# Main.net
KiCad netlist of a schematic drawn in Altium Designer
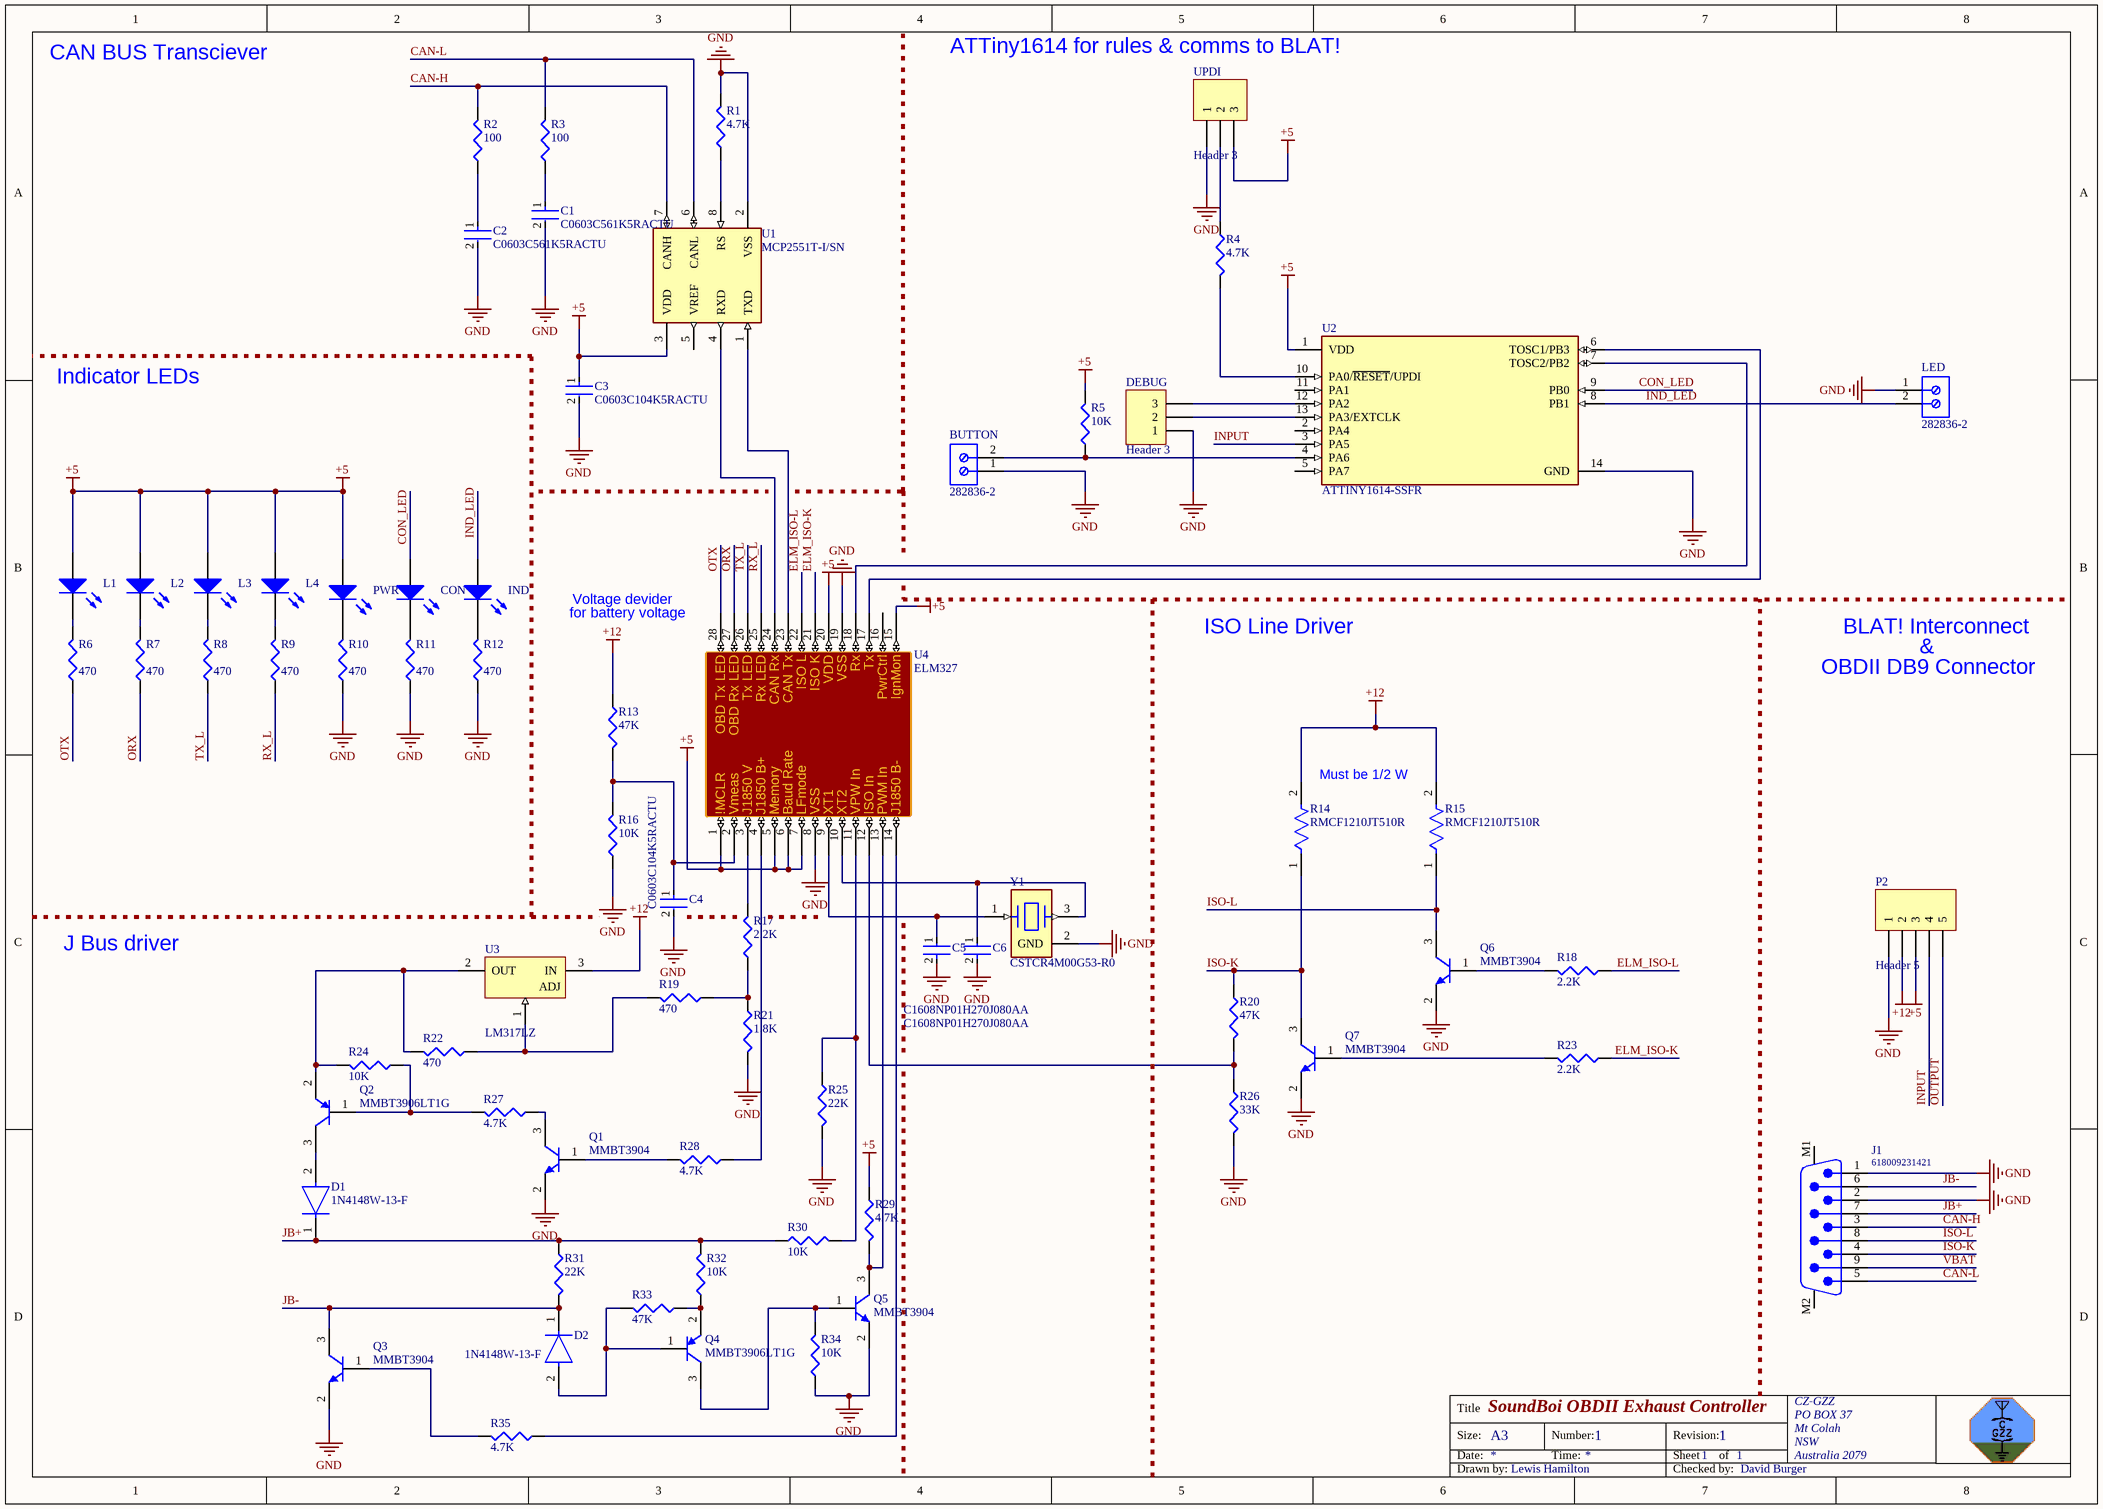
[diagram p0: Main.SchDoc]

(export (version "E")
  (design (tool "Eeschema 10.0.6"))
  (components
    (comp (ref "BUTTON")
      (value "282836-2")
      (footprint "TECO-282836-2_V")
      (description "Female Header, Pitch 5 mm, 1 x 2 Position, Height 10 mm, Tail Length 3.5 mm, Rohs, Bulk")
      (fields (field (name "VOLTAGE") "300V") (field (name "MANUFACTURER") "TE Connectivity"))
      (libsource (lib "Altium Content Vault") (part "CN-1P-F-TB2"))
    )
    (comp (ref "C1")
      (value "C0603C561K5RACTU")
      (footprint "FP-C0603C-CF-MFG")
      (description "CAP CER 560PF 50V X7R 0603")
      (fields
        (field (name "TOLERANCE") "0.1")
        (field (name "OCTOPART") "https://octopart.com/c0603c561k5ractu-kemet-138569")
      )
      (libsource (lib "Altium Content Vault") (part "b4654b650e69147ec39a6b967a45e02"))
    )
    (comp (ref "C2")
      (value "C0603C561K5RACTU")
      (footprint "FP-C0603C-CF-MFG")
      (description "CAP CER 560PF 50V X7R 0603")
      (fields
        (field (name "TOLERANCE") "0.1")
        (field (name "OCTOPART") "https://octopart.com/c0603c561k5ractu-kemet-138569")
      )
      (libsource (lib "Altium Content Vault") (part "b4654b650e69147ec39a6b967a45e02"))
    )
    (comp (ref "C3")
      (value "C0603C104K5RACTU")
      (footprint "FP-C0603C-CF-MFG")
      (description "CAP CER 0.1UF 50V X7R 0603")
      (fields (field (name "TOLERANCE") "0.1") (field (name "MANUFACTURER") "KEMET"))
      (libsource (lib "Altium Content Vault") (part "b4654b650e69147ec39a6b967a45e02"))
    )
    (comp (ref "C4")
      (value "C0603C104K5RACTU")
      (footprint "FP-C0603C-CF-MFG")
      (description "CAP CER 0.1UF 50V X7R 0603")
      (fields (field (name "TOLERANCE") "0.1") (field (name "MANUFACTURER") "KEMET"))
      (libsource (lib "Altium Content Vault") (part "b4654b650e69147ec39a6b967a45e02"))
    )
    (comp (ref "C5")
      (value "C1608NP01H270J080AA")
      (footprint "FP-C1608-080-0_1-IPC_A")
      (description "Multilayer Ceramic Capacitors 27pF ±5% 50V NP0 SMD 0603")
      (fields (field (name "TOLERANCE") "5%"))
      (libsource (lib "Altium Content Vault") (part "236180d848d6139a670b325ea6854c9"))
    )
    (comp (ref "C6")
      (value "C1608NP01H270J080AA")
      (footprint "FP-C1608-080-0_1-IPC_A")
      (description "Multilayer Ceramic Capacitors 27pF ±5% 50V NP0 SMD 0603")
      (fields (field (name "TOLERANCE") "5%"))
      (libsource (lib "Altium Content Vault") (part "236180d848d6139a670b325ea6854c9"))
    )
    (comp (ref "CON")
      (value "LED2")
      (footprint "3.2X1.6X1.1")
      (description "Typical RED, GREEN, YELLOW, AMBER GaAs LED")
      (fields (field (name "PUBLISHER") "Altium Limited"))
      (libsource (lib "Miscellaneous Devices") (part "LED2"))
    )
    (comp (ref "D1")
      (value "1N4148W-13-F")
      (footprint "FP-SOD123-MFG")
      (description "DIODE GEN PURP 100V 150MA SOD123")
      (fields
        (field (name "OCTOPART") "https://octopart.com/1n4148w-13-f-diodes+inc.-2359612")
        (field (name "MANUFACTURER") "Diodes Inc.")
      )
      (libsource (lib "Altium Content Vault") (part "d7152d700b627762746794eb795d46e"))
    )
    (comp (ref "D2")
      (value "1N4148W-13-F")
      (footprint "FP-SOD123-MFG")
      (description "DIODE GEN PURP 100V 150MA SOD123")
      (fields
        (field (name "OCTOPART") "https://octopart.com/1n4148w-13-f-diodes+inc.-2359612")
        (field (name "MANUFACTURER") "Diodes Inc.")
      )
      (libsource (lib "Altium Content Vault") (part "d7152d700b627762746794eb795d46e"))
    )
    (comp (ref "DEBUG")
      (value "Header 3")
      (footprint "HDR1X3")
      (description "Header, 3-Pin")
      (fields (field (name "PUBLISHER") "Altium Limited"))
      (libsource (lib "Miscellaneous Connectors") (part "Header 3"))
    )
    (comp (ref "IND")
      (value "LED2")
      (footprint "3.2X1.6X1.1")
      (description "Typical RED, GREEN, YELLOW, AMBER GaAs LED")
      (fields (field (name "PUBLISHER") "Altium Limited"))
      (libsource (lib "Miscellaneous Devices") (part "LED2"))
    )
    (comp (ref "J1")
      (value "618009231421")
      (footprint "618009231421")
      (description "Male PCB Connector with Hex Screw WR-DSUB, 10.30 mm, Angled, 9 pins")
      (fields (field (name "MANUFACTURER") "Wurth Elektronik") (field (name "PUBLISHER") "WurthElektronik"))
      (libsource (lib "Altium Content Vault") (part "WE-CN-2S-2M-D9"))
    )
    (comp (ref "L1")
      (value "LED2")
      (footprint "3.2X1.6X1.1")
      (description "Typical RED, GREEN, YELLOW, AMBER GaAs LED")
      (fields (field (name "PUBLISHER") "Altium Limited"))
      (libsource (lib "Miscellaneous Devices") (part "LED2"))
    )
    (comp (ref "L2")
      (value "LED2")
      (footprint "3.2X1.6X1.1")
      (description "Typical RED, GREEN, YELLOW, AMBER GaAs LED")
      (fields (field (name "PUBLISHER") "Altium Limited"))
      (libsource (lib "Miscellaneous Devices") (part "LED2"))
    )
    (comp (ref "L3")
      (value "LED2")
      (footprint "3.2X1.6X1.1")
      (description "Typical RED, GREEN, YELLOW, AMBER GaAs LED")
      (fields (field (name "PUBLISHER") "Altium Limited"))
      (libsource (lib "Miscellaneous Devices") (part "LED2"))
    )
    (comp (ref "L4")
      (value "LED2")
      (footprint "3.2X1.6X1.1")
      (description "Typical RED, GREEN, YELLOW, AMBER GaAs LED")
      (fields (field (name "PUBLISHER") "Altium Limited"))
      (libsource (lib "Miscellaneous Devices") (part "LED2"))
    )
    (comp (ref "LED")
      (value "282836-2")
      (footprint "TECO-282836-2_V")
      (description "Female Header, Pitch 5 mm, 1 x 2 Position, Height 10 mm, Tail Length 3.5 mm, Rohs, Bulk")
      (fields (field (name "VOLTAGE") "300V") (field (name "MANUFACTURER") "TE Connectivity"))
      (libsource (lib "Altium Content Vault") (part "CN-1P-F-TB2"))
    )
    (comp (ref "P2")
      (value "Header 5")
      (footprint "HDR1X5")
      (description "Header, 5-Pin")
      (fields (field (name "PUBLISHER") "Altium Limited"))
      (libsource (lib "Miscellaneous Connectors") (part "Header 5"))
    )
    (comp (ref "PWR")
      (value "LED2")
      (footprint "3.2X1.6X1.1")
      (description "Typical RED, GREEN, YELLOW, AMBER GaAs LED")
      (fields (field (name "PUBLISHER") "Altium Limited"))
      (libsource (lib "Miscellaneous Devices") (part "LED2"))
    )
    (comp (ref "Q1")
      (value "MMBT3904")
      (footprint "FAIR-SOT23-3_V")
      (description "NPN General Purpose Amplifier, 40 V, 0.2 A, -55 to 150 degC, 3-Pin SOT23, RoHS, Tape and Reel")
      (fields (field (name "TOLERANCE") "30ppm"))
      (libsource (lib "Altium Content Vault") (part "BJT-NPN-BEC-3"))
    )
    (comp (ref "Q2")
      (value "MMBT3906LT1G")
      (footprint "ONSC-SOT-23-3-318-08_V")
      (description "General Purpose Transistor, PNP Silicon, 3-Pin SOT-23, Pb-Free, Tape and Reel")
      (fields (field (name "MANUFACTURER") "On Semiconductor"))
      (libsource (lib "Altium Content Vault") (part "ONSC-PNP-B1E2C3-3"))
    )
    (comp (ref "Q3")
      (value "MMBT3904")
      (footprint "FAIR-SOT23-3_V")
      (description "NPN General Purpose Amplifier, 40 V, 0.2 A, -55 to 150 degC, 3-Pin SOT23, RoHS, Tape and Reel")
      (fields (field (name "TOLERANCE") "30ppm"))
      (libsource (lib "Altium Content Vault") (part "BJT-NPN-BEC-3"))
    )
    (comp (ref "Q4")
      (value "MMBT3906LT1G")
      (footprint "ONSC-SOT-23-3-318-08_V")
      (description "General Purpose Transistor, PNP Silicon, 3-Pin SOT-23, Pb-Free, Tape and Reel")
      (fields (field (name "MANUFACTURER") "On Semiconductor"))
      (libsource (lib "Altium Content Vault") (part "ONSC-PNP-B1E2C3-3"))
    )
    (comp (ref "Q5")
      (value "MMBT3904")
      (footprint "FAIR-SOT23-3_V")
      (description "NPN General Purpose Amplifier, 40 V, 0.2 A, -55 to 150 degC, 3-Pin SOT23, RoHS, Tape and Reel")
      (fields (field (name "TOLERANCE") "30ppm"))
      (libsource (lib "Altium Content Vault") (part "BJT-NPN-BEC-3"))
    )
    (comp (ref "Q6")
      (value "MMBT3904")
      (footprint "FAIR-SOT23-3_V")
      (description "NPN General Purpose Amplifier, 40 V, 0.2 A, -55 to 150 degC, 3-Pin SOT23, RoHS, Tape and Reel")
      (fields (field (name "TOLERANCE") "30ppm"))
      (libsource (lib "Altium Content Vault") (part "BJT-NPN-BEC-3"))
    )
    (comp (ref "Q7")
      (value "MMBT3904")
      (footprint "FAIR-SOT23-3_V")
      (description "NPN General Purpose Amplifier, 40 V, 0.2 A, -55 to 150 degC, 3-Pin SOT23, RoHS, Tape and Reel")
      (fields (field (name "TOLERANCE") "30ppm"))
      (libsource (lib "Altium Content Vault") (part "BJT-NPN-BEC-3"))
    )
    (comp (ref "R1")
      (value "4.7K")
      (footprint "J1-0603")
      (description "Resistor")
      (fields (field (name "Comment") "Res3") (field (name "PUBLISHER") "Altium Limited"))
      (libsource (lib "Miscellaneous Devices") (part "Res3"))
    )
    (comp (ref "R2")
      (value "100")
      (footprint "J1-0603")
      (description "Resistor")
      (fields (field (name "Comment") "Res3") (field (name "PUBLISHER") "Altium Limited"))
      (libsource (lib "Miscellaneous Devices") (part "Res3"))
    )
    (comp (ref "R3")
      (value "100")
      (footprint "J1-0603")
      (description "Resistor")
      (fields (field (name "Comment") "Res3") (field (name "PUBLISHER") "Altium Limited"))
      (libsource (lib "Miscellaneous Devices") (part "Res3"))
    )
    (comp (ref "R4")
      (value "4.7K")
      (footprint "J1-0603")
      (description "Resistor")
      (fields (field (name "Comment") "Res3") (field (name "PUBLISHER") "Altium Limited"))
      (libsource (lib "Miscellaneous Devices") (part "Res3"))
    )
    (comp (ref "R5")
      (value "10K")
      (footprint "J1-0603")
      (description "Resistor")
      (fields (field (name "Comment") "Res3") (field (name "PUBLISHER") "Altium Limited"))
      (libsource (lib "Miscellaneous Devices") (part "Res3"))
    )
    (comp (ref "R6")
      (value "470")
      (footprint "J1-0603")
      (description "Resistor")
      (fields (field (name "Comment") "Res3") (field (name "PUBLISHER") "Altium Limited"))
      (libsource (lib "Miscellaneous Devices") (part "Res3"))
    )
    (comp (ref "R7")
      (value "470")
      (footprint "J1-0603")
      (description "Resistor")
      (fields (field (name "Comment") "Res3") (field (name "PUBLISHER") "Altium Limited"))
      (libsource (lib "Miscellaneous Devices") (part "Res3"))
    )
    (comp (ref "R8")
      (value "470")
      (footprint "J1-0603")
      (description "Resistor")
      (fields (field (name "Comment") "Res3") (field (name "PUBLISHER") "Altium Limited"))
      (libsource (lib "Miscellaneous Devices") (part "Res3"))
    )
    (comp (ref "R9")
      (value "470")
      (footprint "J1-0603")
      (description "Resistor")
      (fields (field (name "Comment") "Res3") (field (name "PUBLISHER") "Altium Limited"))
      (libsource (lib "Miscellaneous Devices") (part "Res3"))
    )
    (comp (ref "R10")
      (value "470")
      (footprint "J1-0603")
      (description "Resistor")
      (fields (field (name "Comment") "Res3") (field (name "PUBLISHER") "Altium Limited"))
      (libsource (lib "Miscellaneous Devices") (part "Res3"))
    )
    (comp (ref "R11")
      (value "470")
      (footprint "J1-0603")
      (description "Resistor")
      (fields (field (name "Comment") "Res3") (field (name "PUBLISHER") "Altium Limited"))
      (libsource (lib "Miscellaneous Devices") (part "Res3"))
    )
    (comp (ref "R12")
      (value "470")
      (footprint "J1-0603")
      (description "Resistor")
      (fields (field (name "Comment") "Res3") (field (name "PUBLISHER") "Altium Limited"))
      (libsource (lib "Miscellaneous Devices") (part "Res3"))
    )
    (comp (ref "R13")
      (value "47K")
      (footprint "J1-0603")
      (description "Resistor")
      (fields (field (name "Comment") "Res3") (field (name "PUBLISHER") "Altium Limited"))
      (libsource (lib "Miscellaneous Devices") (part "Res3"))
    )
    (comp (ref "R14")
      (value "RMCF1210JT510R")
      (footprint "FP-RMCF1210-MFG")
      (description "510Ω ±5% 0.5W 1210 Thick Film Chip Resistor AEC-Q200 compliant")
      (fields (field (name "TOLERANCE") "5%"))
      (libsource (lib "Altium Content Vault") (part "1029c3af85768c4190bb7ad29bc67b5"))
    )
    (comp (ref "R15")
      (value "RMCF1210JT510R")
      (footprint "FP-RMCF1210-MFG")
      (description "510Ω ±5% 0.5W 1210 Thick Film Chip Resistor AEC-Q200 compliant")
      (fields (field (name "TOLERANCE") "5%"))
      (libsource (lib "Altium Content Vault") (part "1029c3af85768c4190bb7ad29bc67b5"))
    )
    (comp (ref "R16")
      (value "10K")
      (footprint "J1-0603")
      (description "Resistor")
      (fields (field (name "Comment") "Res3") (field (name "PUBLISHER") "Altium Limited"))
      (libsource (lib "Miscellaneous Devices") (part "Res3"))
    )
    (comp (ref "R17")
      (value "2.2K")
      (footprint "J1-0603")
      (description "Resistor")
      (fields (field (name "Comment") "Res3") (field (name "PUBLISHER") "Altium Limited"))
      (libsource (lib "Miscellaneous Devices") (part "Res3"))
    )
    (comp (ref "R18")
      (value "2.2K")
      (footprint "J1-0603")
      (description "Resistor")
      (fields (field (name "Comment") "Res3") (field (name "PUBLISHER") "Altium Limited"))
      (libsource (lib "Miscellaneous Devices") (part "Res3"))
    )
    (comp (ref "R19")
      (value "470")
      (footprint "J1-0603")
      (description "Resistor")
      (fields (field (name "Comment") "Res3") (field (name "PUBLISHER") "Altium Limited"))
      (libsource (lib "Miscellaneous Devices") (part "Res3"))
    )
    (comp (ref "R20")
      (value "47K")
      (footprint "J1-0603")
      (description "Resistor")
      (fields (field (name "Comment") "Res3") (field (name "PUBLISHER") "Altium Limited"))
      (libsource (lib "Miscellaneous Devices") (part "Res3"))
    )
    (comp (ref "R21")
      (value "1.8K")
      (footprint "J1-0603")
      (description "Resistor")
      (fields (field (name "Comment") "Res3") (field (name "PUBLISHER") "Altium Limited"))
      (libsource (lib "Miscellaneous Devices") (part "Res3"))
    )
    (comp (ref "R22")
      (value "470")
      (footprint "J1-0603")
      (description "Resistor")
      (fields (field (name "Comment") "Res3") (field (name "PUBLISHER") "Altium Limited"))
      (libsource (lib "Miscellaneous Devices") (part "Res3"))
    )
    (comp (ref "R23")
      (value "2.2K")
      (footprint "J1-0603")
      (description "Resistor")
      (fields (field (name "Comment") "Res3") (field (name "PUBLISHER") "Altium Limited"))
      (libsource (lib "Miscellaneous Devices") (part "Res3"))
    )
    (comp (ref "R24")
      (value "10K")
      (footprint "J1-0603")
      (description "Resistor")
      (fields (field (name "Comment") "Res3") (field (name "PUBLISHER") "Altium Limited"))
      (libsource (lib "Miscellaneous Devices") (part "Res3"))
    )
    (comp (ref "R25")
      (value "22K")
      (footprint "J1-0603")
      (description "Resistor")
      (fields (field (name "Comment") "Res3") (field (name "PUBLISHER") "Altium Limited"))
      (libsource (lib "Miscellaneous Devices") (part "Res3"))
    )
    (comp (ref "R26")
      (value "33K")
      (footprint "J1-0603")
      (description "Resistor")
      (fields (field (name "Comment") "Res3") (field (name "PUBLISHER") "Altium Limited"))
      (libsource (lib "Miscellaneous Devices") (part "Res3"))
    )
    (comp (ref "R27")
      (value "4.7K")
      (footprint "J1-0603")
      (description "Resistor")
      (fields (field (name "Comment") "Res3") (field (name "PUBLISHER") "Altium Limited"))
      (libsource (lib "Miscellaneous Devices") (part "Res3"))
    )
    (comp (ref "R28")
      (value "4.7K")
      (footprint "J1-0603")
      (description "Resistor")
      (fields (field (name "Comment") "Res3") (field (name "PUBLISHER") "Altium Limited"))
      (libsource (lib "Miscellaneous Devices") (part "Res3"))
    )
    (comp (ref "R29")
      (value "4.7K")
      (footprint "J1-0603")
      (description "Resistor")
      (fields (field (name "Comment") "Res3") (field (name "PUBLISHER") "Altium Limited"))
      (libsource (lib "Miscellaneous Devices") (part "Res3"))
    )
    (comp (ref "R30")
      (value "10K")
      (footprint "J1-0603")
      (description "Resistor")
      (fields (field (name "Comment") "Res3") (field (name "PUBLISHER") "Altium Limited"))
      (libsource (lib "Miscellaneous Devices") (part "Res3"))
    )
    (comp (ref "R31")
      (value "22K")
      (footprint "J1-0603")
      (description "Resistor")
      (fields (field (name "Comment") "Res3") (field (name "PUBLISHER") "Altium Limited"))
      (libsource (lib "Miscellaneous Devices") (part "Res3"))
    )
    (comp (ref "R32")
      (value "10K")
      (footprint "J1-0603")
      (description "Resistor")
      (fields (field (name "Comment") "Res3") (field (name "PUBLISHER") "Altium Limited"))
      (libsource (lib "Miscellaneous Devices") (part "Res3"))
    )
    (comp (ref "R33")
      (value "47K")
      (footprint "J1-0603")
      (description "Resistor")
      (fields (field (name "Comment") "Res3") (field (name "PUBLISHER") "Altium Limited"))
      (libsource (lib "Miscellaneous Devices") (part "Res3"))
    )
    (comp (ref "R34")
      (value "10K")
      (footprint "J1-0603")
      (description "Resistor")
      (fields (field (name "Comment") "Res3") (field (name "PUBLISHER") "Altium Limited"))
      (libsource (lib "Miscellaneous Devices") (part "Res3"))
    )
    (comp (ref "R35")
      (value "4.7K")
      (footprint "J1-0603")
      (description "Resistor")
      (fields (field (name "Comment") "Res3") (field (name "PUBLISHER") "Altium Limited"))
      (libsource (lib "Miscellaneous Devices") (part "Res3"))
    )
    (comp (ref "U1")
      (value "MCP2551T-I/SN")
      (footprint "FP-C04-057-SN-IPC_B")
      (description "IC TRANSCEIVER HALF 1/1 8SOIC")
      (libsource (lib "Altium Content Vault") (part "233f95c99e3dcc4383646026a560a32"))
    )
    (comp (ref "U2")
      (value "ATTINY1614-SSFR")
      (footprint "FP-C04-065-D3X-MFG")
      (description "IC MCU 8BIT 16KB FLASH 14SOIC")
      (fields
        (field (name "MANUFACTURER") "Microchip")
        (field (name "OCTOPART") "https://octopart.com/attiny1614-ssfr-microchip-82181131")
      )
      (libsource (lib "Altium Content Vault") (part "72c199063961b341655dca604db29b7"))
    )
    (comp (ref "U3")
      (value "LM317LZ")
      (footprint "Z03A")
      (description "3-Terminal Adjustable Regulator, 3-pin TO-92")
      (fields (field (name "MANUFACTURER") "National Semiconductor"))
      (libsource (lib "Altium Content Vault") (part "PM-REG-LM1086ADJ-SIL3"))
    )
    (comp (ref "U4") (value "ELM327") (footprint "SOIC28") (libsource (lib "ELM327") (part "ELM327")))
    (comp (ref "UPDI")
      (value "Header 3")
      (footprint "HDR1X3")
      (description "Header, 3-Pin")
      (fields (field (name "PUBLISHER") "Altium Limited"))
      (libsource (lib "") (part "Header 3_1"))
    )
    (comp (ref "Y1")
      (value "CSTCR4M00G53-R0")
      (footprint "FP-CSTCR4M00G53-R0-MFG")
      (description "CERAMIC RES 4.0000MHZ 15PF SMD")
      (fields (field (name "TOLERANCE") "0.5%"))
      (libsource (lib "Altium Content Vault") (part "ef280d15f160a47826ea708296b97d0"))
    )
  )
  (nets
    (net (code "1") (name "+5") (class "Default")
      (node (ref "C3") (pin "1") (pinfunction "1_1") (pintype "passive"))
      (node (ref "L1") (pin "1") (pinfunction "A_1") (pintype "passive"))
      (node (ref "L2") (pin "1") (pinfunction "A_1") (pintype "passive"))
      (node (ref "L3") (pin "1") (pinfunction "A_1") (pintype "passive"))
      (node (ref "L4") (pin "1") (pinfunction "A_1") (pintype "passive"))
      (node (ref "P2") (pin "3") (pinfunction "3_3") (pintype "passive"))
      (node (ref "PWR") (pin "1") (pinfunction "A_1") (pintype "passive"))
      (node (ref "R29") (pin "1") (pinfunction "1_1") (pintype "passive"))
      (node (ref "R5") (pin "2") (pinfunction "2_2") (pintype "passive"))
      (node (ref "U1") (pin "3") (pinfunction "VDD_3") (pintype "power_in"))
      (node (ref "U2") (pin "1") (pinfunction "VDD_1") (pintype "power_in"))
      (node (ref "U4") (pin "1") (pinfunction "1_1") (pintype "bidirectional"))
      (node (ref "U4") (pin "15") (pinfunction "15_15") (pintype "bidirectional"))
      (node (ref "U4") (pin "20") (pinfunction "20_20") (pintype "bidirectional"))
      (node (ref "U4") (pin "5") (pinfunction "5_5") (pintype "bidirectional"))
      (node (ref "U4") (pin "6") (pinfunction "6_6") (pintype "bidirectional"))
      (node (ref "U4") (pin "7") (pinfunction "7_7") (pintype "bidirectional"))
      (node (ref "UPDI") (pin "3") (pinfunction "3_3") (pintype "passive"))
    )
    (net (code "2") (name "+12") (class "Default")
      (node (ref "P2") (pin "2") (pinfunction "2_2") (pintype "passive"))
      (node (ref "R13") (pin "1") (pinfunction "1_1") (pintype "passive"))
      (node (ref "R14") (pin "2") (pinfunction "2_2") (pintype "passive"))
      (node (ref "R15") (pin "2") (pinfunction "2_2") (pintype "passive"))
      (node (ref "U3") (pin "3") (pinfunction "IN_3") (pintype "power_in"))
    )
    (net (code "3") (name "/CAN-H") (class "Default")
      (node (ref "J1") (pin "3") (pinfunction "3_3") (pintype "passive"))
      (node (ref "R2") (pin "2") (pinfunction "2_2") (pintype "passive"))
      (node (ref "U1") (pin "7") (pinfunction "CANH_7") (pintype "bidirectional"))
    )
    (net (code "4") (name "/CAN-L") (class "Default")
      (node (ref "J1") (pin "5") (pinfunction "5_5") (pintype "passive"))
      (node (ref "R3") (pin "2") (pinfunction "2_2") (pintype "passive"))
      (node (ref "U1") (pin "6") (pinfunction "CANL_6") (pintype "bidirectional"))
    )
    (net (code "5") (name "/CON_LED") (class "Default")
      (node (ref "CON") (pin "1") (pinfunction "A_1") (pintype "passive"))
      (node (ref "U2") (pin "9") (pinfunction "PB0_9") (pintype "input"))
    )
    (net (code "6") (name "/ELM_ISO-K") (class "Default")
      (node (ref "R23") (pin "1") (pinfunction "1_1") (pintype "passive"))
      (node (ref "U4") (pin "21") (pinfunction "21_21") (pintype "bidirectional"))
    )
    (net (code "7") (name "/ELM_ISO-L") (class "Default")
      (node (ref "R18") (pin "1") (pinfunction "1_1") (pintype "passive"))
      (node (ref "U4") (pin "22") (pinfunction "22_22") (pintype "bidirectional"))
    )
    (net (code "8") (name "/IND_LED") (class "Default")
      (node (ref "IND") (pin "1") (pinfunction "A_1") (pintype "passive"))
      (node (ref "LED") (pin "2") (pinfunction "2_2") (pintype "passive"))
      (node (ref "U2") (pin "8") (pinfunction "PB1_8") (pintype "input"))
    )
    (net (code "9") (name "/INPUT") (class "Default")
      (node (ref "P2") (pin "4") (pinfunction "4_4") (pintype "passive"))
      (node (ref "U2") (pin "3") (pinfunction "PA5_3") (pintype "input"))
    )
    (net (code "10") (name "/ISO-K") (class "Default")
      (node (ref "J1") (pin "4") (pinfunction "4_4") (pintype "passive"))
      (node (ref "Q7") (pin "3") (pinfunction "C_3") (pintype "passive"))
      (node (ref "R14") (pin "1") (pinfunction "1_1") (pintype "passive"))
      (node (ref "R20") (pin "1") (pinfunction "1_1") (pintype "passive"))
    )
    (net (code "11") (name "/ISO-L") (class "Default")
      (node (ref "J1") (pin "8") (pinfunction "8_8") (pintype "passive"))
      (node (ref "Q6") (pin "3") (pinfunction "C_3") (pintype "passive"))
      (node (ref "R15") (pin "1") (pinfunction "1_1") (pintype "passive"))
    )
    (net (code "12") (name "/JB+") (class "Default")
      (node (ref "D1") (pin "1") (pinfunction "C_1") (pintype "passive"))
      (node (ref "J1") (pin "7") (pinfunction "7_7") (pintype "passive"))
      (node (ref "R30") (pin "1") (pinfunction "1_1") (pintype "passive"))
      (node (ref "R31") (pin "1") (pinfunction "1_1") (pintype "passive"))
      (node (ref "R32") (pin "2") (pinfunction "2_2") (pintype "passive"))
    )
    (net (code "13") (name "/JB-") (class "Default")
      (node (ref "D2") (pin "1") (pinfunction "C_1") (pintype "passive"))
      (node (ref "J1") (pin "6") (pinfunction "6_6") (pintype "passive"))
      (node (ref "Q3") (pin "3") (pinfunction "C_3") (pintype "passive"))
      (node (ref "R31") (pin "2") (pinfunction "2_2") (pintype "passive"))
    )
    (net (code "14") (name "/ORX") (class "Default")
      (node (ref "R7") (pin "1") (pinfunction "1_1") (pintype "passive"))
      (node (ref "U4") (pin "27") (pinfunction "27_27") (pintype "bidirectional"))
    )
    (net (code "15") (name "/OTX") (class "Default")
      (node (ref "R6") (pin "1") (pinfunction "1_1") (pintype "passive"))
      (node (ref "U4") (pin "28") (pinfunction "28_28") (pintype "bidirectional"))
    )
    (net (code "16") (name "/OUTPUT") (class "Default")
      (node (ref "P2") (pin "5") (pinfunction "5_5") (pintype "passive"))
    )
    (net (code "17") (name "/RX_L") (class "Default")
      (node (ref "R9") (pin "1") (pinfunction "1_1") (pintype "passive"))
      (node (ref "U4") (pin "25") (pinfunction "25_25") (pintype "bidirectional"))
    )
    (net (code "18") (name "/TX_L") (class "Default")
      (node (ref "R8") (pin "1") (pinfunction "1_1") (pintype "passive"))
      (node (ref "U4") (pin "26") (pinfunction "26_26") (pintype "bidirectional"))
    )
    (net (code "19") (name "/VBAT") (class "Default")
      (node (ref "J1") (pin "9") (pinfunction "9_9") (pintype "passive"))
    )
    (net (code "20") (name "GND") (class "Default")
      (node (ref "BUTTON") (pin "1") (pinfunction "1_1") (pintype "passive"))
      (node (ref "C1") (pin "2") (pinfunction "2_2") (pintype "passive"))
      (node (ref "C2") (pin "2") (pinfunction "2_2") (pintype "passive"))
      (node (ref "C3") (pin "2") (pinfunction "2_2") (pintype "passive"))
      (node (ref "C4") (pin "2") (pinfunction "2_2") (pintype "passive"))
      (node (ref "C5") (pin "2") (pinfunction "2_2") (pintype "passive"))
      (node (ref "C6") (pin "2") (pinfunction "2_2") (pintype "passive"))
      (node (ref "DEBUG") (pin "1") (pinfunction "1_1") (pintype "passive"))
      (node (ref "J1") (pin "1") (pinfunction "1_1") (pintype "passive"))
      (node (ref "J1") (pin "2") (pinfunction "2_2") (pintype "passive"))
      (node (ref "LED") (pin "1") (pinfunction "1_1") (pintype "passive"))
      (node (ref "P2") (pin "1") (pinfunction "1_1") (pintype "passive"))
      (node (ref "Q1") (pin "2") (pinfunction "E_2") (pintype "passive"))
      (node (ref "Q3") (pin "2") (pinfunction "E_2") (pintype "passive"))
      (node (ref "Q5") (pin "2") (pinfunction "E_2") (pintype "passive"))
      (node (ref "Q6") (pin "2") (pinfunction "E_2") (pintype "passive"))
      (node (ref "Q7") (pin "2") (pinfunction "E_2") (pintype "passive"))
      (node (ref "R1") (pin "2") (pinfunction "2_2") (pintype "passive"))
      (node (ref "R10") (pin "1") (pinfunction "1_1") (pintype "passive"))
      (node (ref "R11") (pin "1") (pinfunction "1_1") (pintype "passive"))
      (node (ref "R12") (pin "1") (pinfunction "1_1") (pintype "passive"))
      (node (ref "R16") (pin "1") (pinfunction "1_1") (pintype "passive"))
      (node (ref "R21") (pin "2") (pinfunction "2_2") (pintype "passive"))
      (node (ref "R25") (pin "2") (pinfunction "2_2") (pintype "passive"))
      (node (ref "R26") (pin "2") (pinfunction "2_2") (pintype "passive"))
      (node (ref "R34") (pin "1") (pinfunction "1_1") (pintype "passive"))
      (node (ref "U1") (pin "2") (pinfunction "VSS_2") (pintype "power_in"))
      (node (ref "U2") (pin "14") (pinfunction "GND_14") (pintype "power_in"))
      (node (ref "U4") (pin "19") (pinfunction "19_19") (pintype "bidirectional"))
      (node (ref "U4") (pin "8") (pinfunction "8_8") (pintype "bidirectional"))
      (node (ref "UPDI") (pin "1") (pinfunction "1_1") (pintype "passive"))
      (node (ref "Y1") (pin "2") (pinfunction "GND_2") (pintype "power_in"))
    )
    (net (code "21") (name "Net-(C1-Pad1)") (class "Default")
      (node (ref "C1") (pin "1") (pinfunction "1_1") (pintype "passive"))
      (node (ref "R3") (pin "1") (pinfunction "1_1") (pintype "passive"))
    )
    (net (code "22") (name "Net-(C2-Pad1)") (class "Default")
      (node (ref "C2") (pin "1") (pinfunction "1_1") (pintype "passive"))
      (node (ref "R2") (pin "1") (pinfunction "1_1") (pintype "passive"))
    )
    (net (code "23") (name "Net-(C4-Pad1)") (class "Default")
      (node (ref "C4") (pin "1") (pinfunction "1_1") (pintype "passive"))
      (node (ref "R13") (pin "2") (pinfunction "2_2") (pintype "passive"))
      (node (ref "R16") (pin "2") (pinfunction "2_2") (pintype "passive"))
      (node (ref "U4") (pin "2") (pinfunction "2_2") (pintype "bidirectional"))
    )
    (net (code "24") (name "Net-(CON-K)") (class "Default")
      (node (ref "CON") (pin "2") (pinfunction "K_2") (pintype "passive"))
      (node (ref "R11") (pin "2") (pinfunction "2_2") (pintype "passive"))
    )
    (net (code "25") (name "Net-(D1-A)") (class "Default")
      (node (ref "D1") (pin "2") (pinfunction "A_2") (pintype "passive"))
      (node (ref "Q2") (pin "3") (pinfunction "C_3") (pintype "passive"))
    )
    (net (code "26") (name "Net-(D2-A)") (class "Default")
      (node (ref "D2") (pin "2") (pinfunction "A_2") (pintype "passive"))
      (node (ref "Q4") (pin "1") (pinfunction "B_1") (pintype "passive"))
      (node (ref "R33") (pin "2") (pinfunction "2_2") (pintype "passive"))
    )
    (net (code "27") (name "Net-(IND-K)") (class "Default")
      (node (ref "IND") (pin "2") (pinfunction "K_2") (pintype "passive"))
      (node (ref "R12") (pin "2") (pinfunction "2_2") (pintype "passive"))
    )
    (net (code "28") (name "Net-(L1-K)") (class "Default")
      (node (ref "L1") (pin "2") (pinfunction "K_2") (pintype "passive"))
      (node (ref "R6") (pin "2") (pinfunction "2_2") (pintype "passive"))
    )
    (net (code "29") (name "Net-(L2-K)") (class "Default")
      (node (ref "L2") (pin "2") (pinfunction "K_2") (pintype "passive"))
      (node (ref "R7") (pin "2") (pinfunction "2_2") (pintype "passive"))
    )
    (net (code "30") (name "Net-(L3-K)") (class "Default")
      (node (ref "L3") (pin "2") (pinfunction "K_2") (pintype "passive"))
      (node (ref "R8") (pin "2") (pinfunction "2_2") (pintype "passive"))
    )
    (net (code "31") (name "Net-(L4-K)") (class "Default")
      (node (ref "L4") (pin "2") (pinfunction "K_2") (pintype "passive"))
      (node (ref "R9") (pin "2") (pinfunction "2_2") (pintype "passive"))
    )
    (net (code "32") (name "Net-(PWR-K)") (class "Default")
      (node (ref "PWR") (pin "2") (pinfunction "K_2") (pintype "passive"))
      (node (ref "R10") (pin "2") (pinfunction "2_2") (pintype "passive"))
    )
    (net (code "33") (name "Net-(Q1-B)") (class "Default")
      (node (ref "Q1") (pin "1") (pinfunction "B_1") (pintype "passive"))
      (node (ref "R28") (pin "2") (pinfunction "2_2") (pintype "passive"))
    )
    (net (code "34") (name "Net-(Q1-C)") (class "Default")
      (node (ref "Q1") (pin "3") (pinfunction "C_3") (pintype "passive"))
      (node (ref "R27") (pin "1") (pinfunction "1_1") (pintype "passive"))
    )
    (net (code "35") (name "Net-(Q2-B)") (class "Default")
      (node (ref "Q2") (pin "1") (pinfunction "B_1") (pintype "passive"))
      (node (ref "R24") (pin "1") (pinfunction "1_1") (pintype "passive"))
      (node (ref "R27") (pin "2") (pinfunction "2_2") (pintype "passive"))
    )
    (net (code "36") (name "Net-(Q2-E)") (class "Default")
      (node (ref "Q2") (pin "2") (pinfunction "E_2") (pintype "passive"))
      (node (ref "R22") (pin "2") (pinfunction "2_2") (pintype "passive"))
      (node (ref "R24") (pin "2") (pinfunction "2_2") (pintype "passive"))
      (node (ref "U3") (pin "2") (pinfunction "OUT_2") (pintype "power_in"))
    )
    (net (code "37") (name "Net-(Q3-B)") (class "Default")
      (node (ref "Q3") (pin "1") (pinfunction "B_1") (pintype "passive"))
      (node (ref "R35") (pin "2") (pinfunction "2_2") (pintype "passive"))
    )
    (net (code "38") (name "Net-(Q4-C)") (class "Default")
      (node (ref "Q4") (pin "3") (pinfunction "C_3") (pintype "passive"))
      (node (ref "Q5") (pin "1") (pinfunction "B_1") (pintype "passive"))
      (node (ref "R34") (pin "2") (pinfunction "2_2") (pintype "passive"))
    )
    (net (code "39") (name "Net-(Q4-E)") (class "Default")
      (node (ref "Q4") (pin "2") (pinfunction "E_2") (pintype "passive"))
      (node (ref "R32") (pin "1") (pinfunction "1_1") (pintype "passive"))
      (node (ref "R33") (pin "1") (pinfunction "1_1") (pintype "passive"))
    )
    (net (code "40") (name "Net-(Q5-C)") (class "Default")
      (node (ref "Q5") (pin "3") (pinfunction "C_3") (pintype "passive"))
      (node (ref "R29") (pin "2") (pinfunction "2_2") (pintype "passive"))
      (node (ref "U4") (pin "13") (pinfunction "13_13") (pintype "bidirectional"))
    )
    (net (code "41") (name "Net-(Q6-B)") (class "Default")
      (node (ref "Q6") (pin "1") (pinfunction "B_1") (pintype "passive"))
      (node (ref "R18") (pin "2") (pinfunction "2_2") (pintype "passive"))
    )
    (net (code "42") (name "Net-(Q7-B)") (class "Default")
      (node (ref "Q7") (pin "1") (pinfunction "B_1") (pintype "passive"))
      (node (ref "R23") (pin "2") (pinfunction "2_2") (pintype "passive"))
    )
    (net (code "43") (name "Net-(R4-Pad1)") (class "Default")
      (node (ref "R4") (pin "1") (pinfunction "1_1") (pintype "passive"))
      (node (ref "UPDI") (pin "2") (pinfunction "2_2") (pintype "passive"))
    )
    (net (code "44") (name "Net-(R17-Pad1)") (class "Default")
      (node (ref "R17") (pin "1") (pinfunction "1_1") (pintype "passive"))
      (node (ref "R19") (pin "1") (pinfunction "1_1") (pintype "passive"))
      (node (ref "R21") (pin "1") (pinfunction "1_1") (pintype "passive"))
    )
    (net (code "45") (name "Net-(R17-Pad2)") (class "Default")
      (node (ref "R17") (pin "2") (pinfunction "2_2") (pintype "passive"))
      (node (ref "U4") (pin "3") (pinfunction "3_3") (pintype "bidirectional"))
    )
    (net (code "46") (name "Net-(R20-Pad2)") (class "Default")
      (node (ref "R20") (pin "2") (pinfunction "2_2") (pintype "passive"))
      (node (ref "R26") (pin "1") (pinfunction "1_1") (pintype "passive"))
      (node (ref "U4") (pin "12") (pinfunction "12_12") (pintype "bidirectional"))
    )
    (net (code "47") (name "Net-(R25-Pad1)") (class "Default")
      (node (ref "R25") (pin "1") (pinfunction "1_1") (pintype "passive"))
      (node (ref "R30") (pin "2") (pinfunction "2_2") (pintype "passive"))
      (node (ref "U4") (pin "11") (pinfunction "11_11") (pintype "bidirectional"))
    )
    (net (code "48") (name "Net-(R28-Pad1)") (class "Default")
      (node (ref "R28") (pin "1") (pinfunction "1_1") (pintype "passive"))
      (node (ref "U4") (pin "4") (pinfunction "4_4") (pintype "bidirectional"))
    )
    (net (code "49") (name "Net-(R35-Pad1)") (class "Default")
      (node (ref "R35") (pin "1") (pinfunction "1_1") (pintype "passive"))
      (node (ref "U4") (pin "14") (pinfunction "14_14") (pintype "bidirectional"))
    )
    (net (code "50") (name "Net-(U1-RS)") (class "Default")
      (node (ref "R1") (pin "1") (pinfunction "1_1") (pintype "passive"))
      (node (ref "U1") (pin "8") (pinfunction "RS_8") (pintype "input"))
    )
    (net (code "51") (name "Net-(U1-RXD)") (class "Default")
      (node (ref "U1") (pin "4") (pinfunction "RXD_4") (pintype "output"))
      (node (ref "U4") (pin "24") (pinfunction "24_24") (pintype "bidirectional"))
    )
    (net (code "52") (name "Net-(U1-TXD)") (class "Default")
      (node (ref "U1") (pin "1") (pinfunction "TXD_1") (pintype "input"))
      (node (ref "U4") (pin "23") (pinfunction "23_23") (pintype "bidirectional"))
    )
    (net (code "53") (name "Net-(U2-PA0{slash}~{RESET}{slash}UPDI)") (class "Default")
      (node (ref "R4") (pin "2") (pinfunction "2_2") (pintype "passive"))
      (node (ref "U2") (pin "10") (pinfunction "PA0/~{RESET}/UPDI_10") (pintype "input"))
    )
    (net (code "54") (name "Net-(U2-PA2)") (class "Default")
      (node (ref "DEBUG") (pin "3") (pinfunction "3_3") (pintype "passive"))
      (node (ref "U2") (pin "12") (pinfunction "PA2_12") (pintype "input"))
    )
    (net (code "55") (name "Net-(U2-PA3{slash}EXTCLK)") (class "Default")
      (node (ref "DEBUG") (pin "2") (pinfunction "2_2") (pintype "passive"))
      (node (ref "U2") (pin "13") (pinfunction "PA3/EXTCLK_13") (pintype "input"))
    )
    (net (code "56") (name "Net-(U2-PA6)") (class "Default")
      (node (ref "BUTTON") (pin "2") (pinfunction "2_2") (pintype "passive"))
      (node (ref "R5") (pin "1") (pinfunction "1_1") (pintype "passive"))
      (node (ref "U2") (pin "4") (pinfunction "PA6_4") (pintype "input"))
    )
    (net (code "57") (name "Net-(U2-TOSC1{slash}PB3)") (class "Default")
      (node (ref "U2") (pin "6") (pinfunction "TOSC1/PB3_6") (pintype "bidirectional"))
      (node (ref "U4") (pin "17") (pinfunction "17_17") (pintype "bidirectional"))
    )
    (net (code "58") (name "Net-(U2-TOSC2{slash}PB2)") (class "Default")
      (node (ref "U2") (pin "7") (pinfunction "TOSC2/PB2_7") (pintype "bidirectional"))
      (node (ref "U4") (pin "18") (pinfunction "18_18") (pintype "bidirectional"))
    )
    (net (code "59") (name "Net-(U3-ADJ)") (class "Default")
      (node (ref "R19") (pin "2") (pinfunction "2_2") (pintype "passive"))
      (node (ref "R22") (pin "1") (pinfunction "1_1") (pintype "passive"))
      (node (ref "U3") (pin "1") (pinfunction "ADJ_1") (pintype "input"))
    )
    (net (code "60") (name "Net-(Y1-Input)") (class "Default")
      (node (ref "C5") (pin "1") (pinfunction "1_1") (pintype "passive"))
      (node (ref "U4") (pin "9") (pinfunction "9_9") (pintype "bidirectional"))
      (node (ref "Y1") (pin "1") (pinfunction "Input_1") (pintype "input"))
    )
    (net (code "61") (name "Net-(Y1-Output)") (class "Default")
      (node (ref "C6") (pin "1") (pinfunction "1_1") (pintype "passive"))
      (node (ref "U4") (pin "10") (pinfunction "10_10") (pintype "bidirectional"))
      (node (ref "Y1") (pin "3") (pinfunction "Output_3") (pintype "output"))
    )
    (net (code "62") (name "unconnected-(J1-PadM1)") (class "Default")
      (node (ref "J1") (pin "M1") (pinfunction "M1_M1") (pintype "passive"))
    )
    (net (code "63") (name "unconnected-(J1-PadM2)") (class "Default")
      (node (ref "J1") (pin "M2") (pinfunction "M2_M2") (pintype "passive"))
    )
    (net (code "64") (name "unconnected-(U1-VREF-Pad5)") (class "Default")
      (node (ref "U1") (pin "5") (pinfunction "VREF_5") (pintype "output"))
    )
    (net (code "65") (name "unconnected-(U2-PA1-Pad11)") (class "Default")
      (node (ref "U2") (pin "11") (pinfunction "PA1_11") (pintype "input"))
    )
    (net (code "66") (name "unconnected-(U2-PA4-Pad2)") (class "Default")
      (node (ref "U2") (pin "2") (pinfunction "PA4_2") (pintype "input"))
    )
    (net (code "67") (name "unconnected-(U2-PA7-Pad5)") (class "Default")
      (node (ref "U2") (pin "5") (pinfunction "PA7_5") (pintype "input"))
    )
    (net (code "68") (name "unconnected-(U4-Pad16)") (class "Default")
      (node (ref "U4") (pin "16") (pinfunction "16_16") (pintype "bidirectional"))
    )
  )
)
